# Microcontroller.net
KiCad netlist of a schematic drawn in Altium Designer
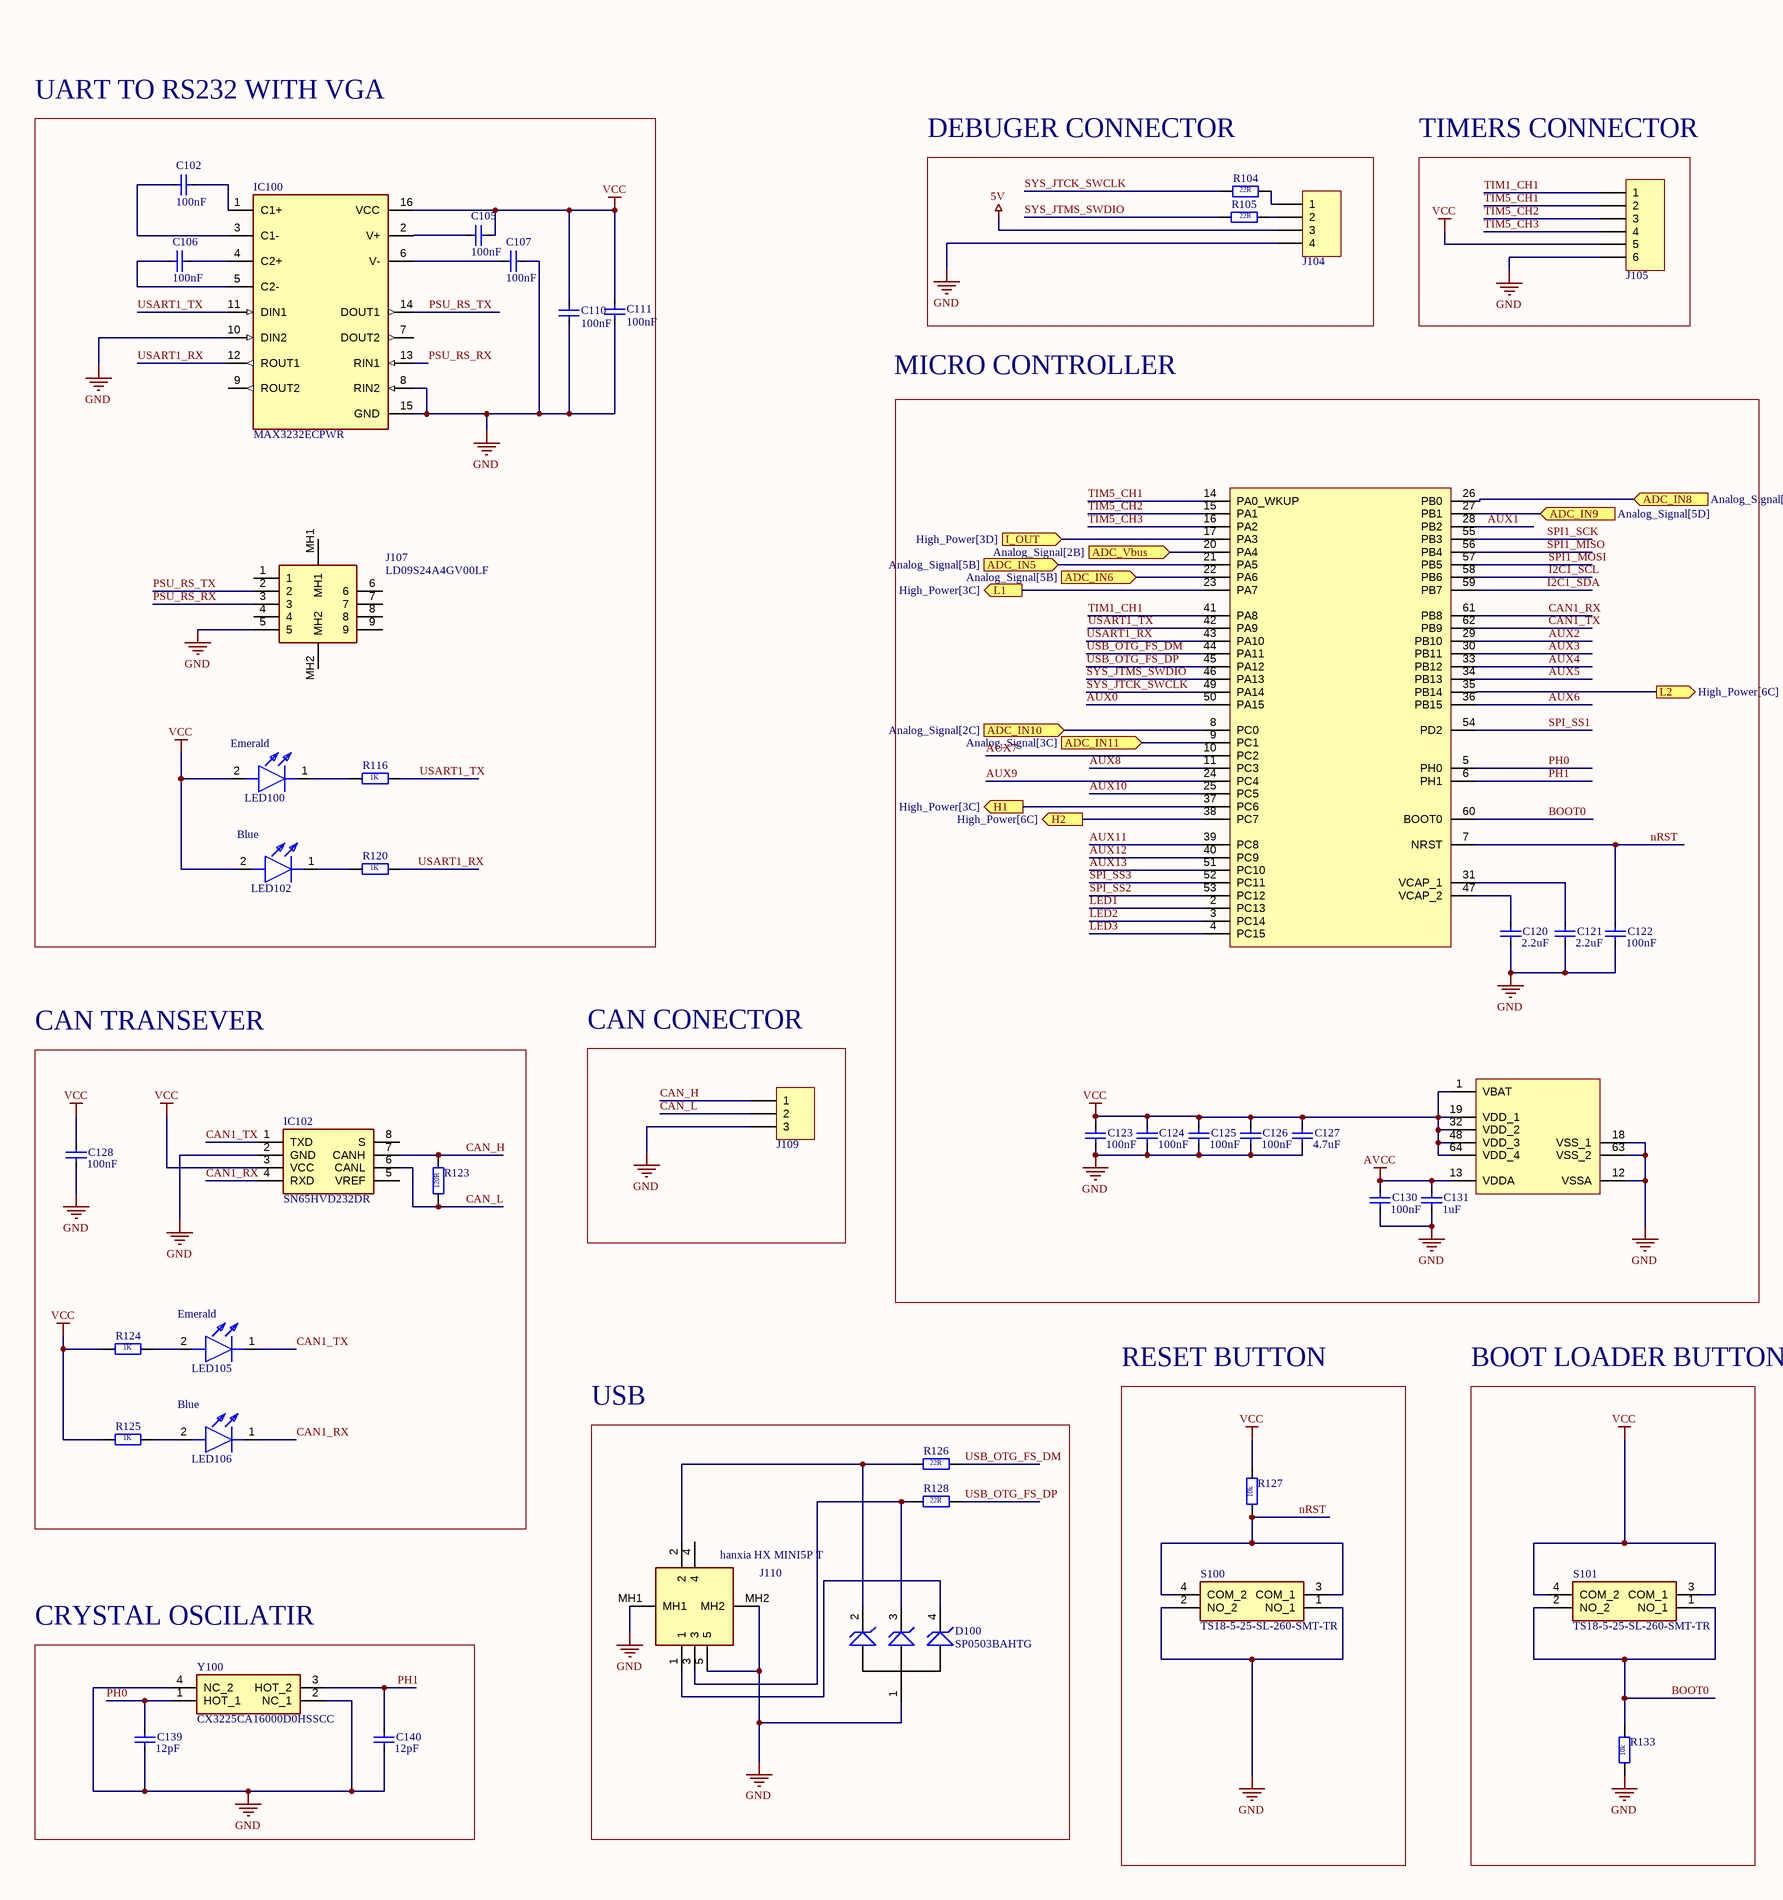
[diagram p0: Microcontroller.SchDoc, left]
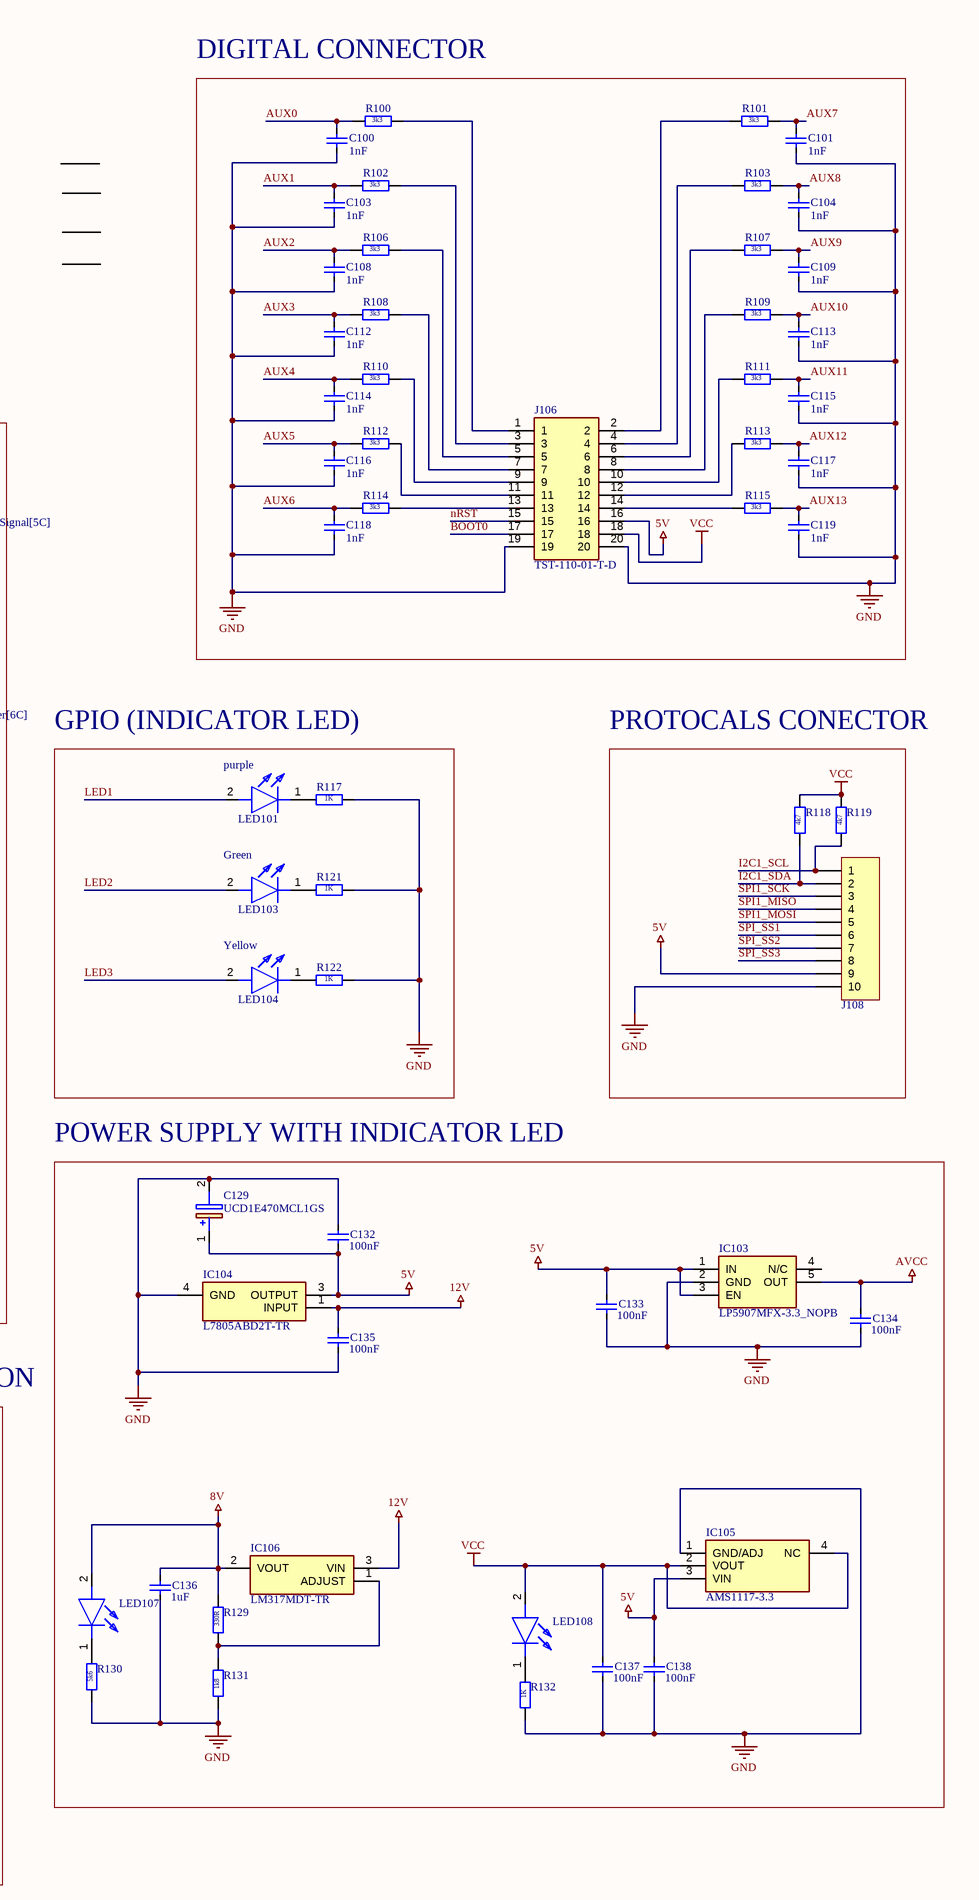
[diagram p1: Microcontroller.SchDoc, right]

(export (version "E")
  (design (tool "Eeschema 10.0.6"))
  (components
    (comp (ref "C100")
      (value "1nF")
      (footprint "CAPC1608X09N")
      (fields (field (name "MPN") "CC0603KRX7R9BB102") (field (name "Comment") "C"))
      (libsource (lib "My_lib") (part "C"))
    )
    (comp (ref "C101")
      (value "1nF")
      (footprint "CAPC1608X09N")
      (fields (field (name "MPN") "CC0603KRX7R9BB102") (field (name "Comment") "C"))
      (libsource (lib "My_lib") (part "C"))
    )
    (comp (ref "C102")
      (value "100nF")
      (footprint "CAPC1608X09N")
      (fields (field (name "MPN") "06033C104KAT4A") (field (name "Comment") "C"))
      (libsource (lib "My_lib") (part "C"))
    )
    (comp (ref "C103")
      (value "1nF")
      (footprint "CAPC1608X09N")
      (fields (field (name "MPN") "CC0603KRX7R9BB102") (field (name "Comment") "C"))
      (libsource (lib "My_lib") (part "C"))
    )
    (comp (ref "C104")
      (value "1nF")
      (footprint "CAPC1608X09N")
      (fields (field (name "MPN") "CC0603KRX7R9BB102") (field (name "Comment") "C"))
      (libsource (lib "My_lib") (part "C"))
    )
    (comp (ref "C105")
      (value "100nF")
      (footprint "CAPC1608X09N")
      (fields (field (name "MPN") "06033C104KAT4A") (field (name "Comment") "C"))
      (libsource (lib "My_lib") (part "C"))
    )
    (comp (ref "C106")
      (value "100nF")
      (footprint "CAPC1608X09N")
      (fields (field (name "MPN") "06033C104KAT4A") (field (name "Comment") "C"))
      (libsource (lib "My_lib") (part "C"))
    )
    (comp (ref "C107")
      (value "100nF")
      (footprint "CAPC1608X09N")
      (fields (field (name "MPN") "06033C104KAT4A") (field (name "Comment") "C"))
      (libsource (lib "My_lib") (part "C"))
    )
    (comp (ref "C108")
      (value "1nF")
      (footprint "CAPC1608X09N")
      (fields (field (name "MPN") "CC0603KRX7R9BB102") (field (name "Comment") "C"))
      (libsource (lib "My_lib") (part "C"))
    )
    (comp (ref "C109")
      (value "1nF")
      (footprint "CAPC1608X09N")
      (fields (field (name "MPN") "CC0603KRX7R9BB102") (field (name "Comment") "C"))
      (libsource (lib "My_lib") (part "C"))
    )
    (comp (ref "C110")
      (value "100nF")
      (footprint "CAPC1608X09N")
      (fields (field (name "MPN") "06033C104KAT4A") (field (name "Comment") "C"))
      (libsource (lib "My_lib") (part "C"))
    )
    (comp (ref "C111")
      (value "100nF")
      (footprint "CAPC1608X09N")
      (fields (field (name "MPN") "06033C104KAT4A") (field (name "Comment") "C"))
      (libsource (lib "My_lib") (part "C"))
    )
    (comp (ref "C112")
      (value "1nF")
      (footprint "CAPC1608X09N")
      (fields (field (name "MPN") "CC0603KRX7R9BB102") (field (name "Comment") "C"))
      (libsource (lib "My_lib") (part "C"))
    )
    (comp (ref "C113")
      (value "1nF")
      (footprint "CAPC1608X09N")
      (fields (field (name "MPN") "CC0603KRX7R9BB102") (field (name "Comment") "C"))
      (libsource (lib "My_lib") (part "C"))
    )
    (comp (ref "C114")
      (value "1nF")
      (footprint "CAPC1608X09N")
      (fields (field (name "MPN") "CC0603KRX7R9BB102") (field (name "Comment") "C"))
      (libsource (lib "My_lib") (part "C"))
    )
    (comp (ref "C115")
      (value "1nF")
      (footprint "CAPC1608X09N")
      (fields (field (name "MPN") "CC0603KRX7R9BB102") (field (name "Comment") "C"))
      (libsource (lib "My_lib") (part "C"))
    )
    (comp (ref "C116")
      (value "1nF")
      (footprint "CAPC1608X09N")
      (fields (field (name "MPN") "CC0603KRX7R9BB102") (field (name "Comment") "C"))
      (libsource (lib "My_lib") (part "C"))
    )
    (comp (ref "C117")
      (value "1nF")
      (footprint "CAPC1608X09N")
      (fields (field (name "MPN") "CC0603KRX7R9BB102") (field (name "Comment") "C"))
      (libsource (lib "My_lib") (part "C"))
    )
    (comp (ref "C118")
      (value "1nF")
      (footprint "CAPC1608X09N")
      (fields (field (name "MPN") "CC0603KRX7R9BB102") (field (name "Comment") "C"))
      (libsource (lib "My_lib") (part "C"))
    )
    (comp (ref "C119")
      (value "1nF")
      (footprint "CAPC1608X09N")
      (fields (field (name "MPN") "CC0603KRX7R9BB102") (field (name "Comment") "C"))
      (libsource (lib "My_lib") (part "C"))
    )
    (comp (ref "C120")
      (value "2.2uF")
      (footprint "CAPC1608X09N")
      (fields (field (name "MPN") "0603B225K250NT") (field (name "Comment") "C"))
      (libsource (lib "My_lib") (part "C"))
    )
    (comp (ref "C121")
      (value "2.2uF")
      (footprint "CAPC1608X09N")
      (fields (field (name "MPN") "0603B225K250NT") (field (name "Comment") "C"))
      (libsource (lib "My_lib") (part "C"))
    )
    (comp (ref "C122")
      (value "100nF")
      (footprint "CAPC1608X09N")
      (fields (field (name "MPN") "06033C104KAT4A") (field (name "Comment") "C"))
      (libsource (lib "My_lib") (part "C"))
    )
    (comp (ref "C123")
      (value "100nF")
      (footprint "CAPC1608X09N")
      (fields (field (name "MPN") "06033C104KAT4A") (field (name "Comment") "C"))
      (libsource (lib "My_lib") (part "C"))
    )
    (comp (ref "C124")
      (value "100nF")
      (footprint "CAPC1608X09N")
      (fields (field (name "MPN") "06033C104KAT4A") (field (name "Comment") "C"))
      (libsource (lib "My_lib") (part "C"))
    )
    (comp (ref "C125")
      (value "100nF")
      (footprint "CAPC1608X09N")
      (fields (field (name "MPN") "06033C104KAT4A") (field (name "Comment") "C"))
      (libsource (lib "My_lib") (part "C"))
    )
    (comp (ref "C126")
      (value "100nF")
      (footprint "CAPC1608X09N")
      (fields (field (name "MPN") "06033C104KAT4A") (field (name "Comment") "C"))
      (libsource (lib "My_lib") (part "C"))
    )
    (comp (ref "C127")
      (value "4.7uF")
      (footprint "CAPC3216X18N")
      (fields (field (name "MPN") "CS3216X7R475K160NRI") (field (name "Comment") "C"))
      (libsource (lib "My_lib") (part "C"))
    )
    (comp (ref "C128")
      (value "100nF")
      (footprint "CAPC1608X09N")
      (fields (field (name "MPN") "06033C104KAT4A") (field (name "Comment") "C"))
      (libsource (lib "My_lib") (part "C"))
    )
    (comp (ref "C129")
      (value "UCD1E470MCL1GS")
      (footprint "SamacSys:CAPAE660X610N")
      (description "Capacitor Polarised")
      (fields (field (name "LCSC PART NUMBER") "C308827"))
      (libsource (lib "*") (part "UCD1E470MCL1GS"))
    )
    (comp (ref "C130")
      (value "100nF")
      (footprint "CAPC1608X09N")
      (fields (field (name "MPN") "06033C104KAT4A") (field (name "Comment") "C"))
      (libsource (lib "My_lib") (part "C"))
    )
    (comp (ref "C131")
      (value "1uF")
      (footprint "CAPC1608X09N")
      (fields (field (name "MPN") "CL10B105KP8NNNC") (field (name "Comment") "C"))
      (libsource (lib "My_lib") (part "C"))
    )
    (comp (ref "C132")
      (value "100nF")
      (footprint "CAPC1608X09N")
      (fields (field (name "MPN") "06033C104KAT4A") (field (name "Comment") "C"))
      (libsource (lib "My_lib") (part "C"))
    )
    (comp (ref "C133")
      (value "100nF")
      (footprint "CAPC1608X09N")
      (fields (field (name "MPN") "06033C104KAT4A") (field (name "Comment") "C"))
      (libsource (lib "My_lib") (part "C"))
    )
    (comp (ref "C134")
      (value "100nF")
      (footprint "CAPC1608X09N")
      (fields (field (name "MPN") "06033C104KAT4A") (field (name "Comment") "C"))
      (libsource (lib "My_lib") (part "C"))
    )
    (comp (ref "C135")
      (value "100nF")
      (footprint "CAPC1608X09N")
      (fields (field (name "MPN") "06033C104KAT4A") (field (name "Comment") "C"))
      (libsource (lib "My_lib") (part "C"))
    )
    (comp (ref "C136")
      (value "1uF")
      (footprint "CAPC1608X09N")
      (fields (field (name "MPN") "CL10B105KP8NNNC") (field (name "Comment") "C"))
      (libsource (lib "My_lib") (part "C"))
    )
    (comp (ref "C137")
      (value "100nF")
      (footprint "CAPC1608X09N")
      (fields (field (name "MPN") "06033C104KAT4A") (field (name "Comment") "C"))
      (libsource (lib "My_lib") (part "C"))
    )
    (comp (ref "C138")
      (value "100nF")
      (footprint "CAPC1608X09N")
      (fields (field (name "MPN") "06033C104KAT4A") (field (name "Comment") "C"))
      (libsource (lib "My_lib") (part "C"))
    )
    (comp (ref "C139")
      (value "12pF")
      (footprint "CAPC1608X09N")
      (fields (field (name "MPN") "CL10C120JB8NNNC") (field (name "Comment") "C"))
      (libsource (lib "My_lib") (part "C"))
    )
    (comp (ref "C140")
      (value "12pF")
      (footprint "CAPC1608X09N")
      (fields (field (name "MPN") "CL10C120JB8NNNC") (field (name "Comment") "C"))
      (libsource (lib "My_lib") (part "C"))
    )
    (comp (ref "D100")
      (value "SP0503BAHTG")
      (footprint "SamacSys:SP0503BAHTG")
      (description "TVS Diode (Uni-directional)")
      (fields (field (name "LCSC PART NUMBER") "C41364459"))
      (libsource (lib "SamacSys") (part "SP0503BAHTG"))
    )
    (comp (ref "IC100")
      (value "MAX3232ECPWR")
      (footprint "SamacSys:SOP65P640X120-16N")
      (description "Integrated Circuit")
      (fields (field (name "LCSC PART NUMBER") "C11317"))
      (libsource (lib "SamacSys") (part "MAX3232ECPWR"))
    )
    (comp (ref "IC101")
      (value "STM32F405RGT6")
      (footprint "SamacSys:QFP50P1200X1200X160-64N")
      (description "Integrated Circuit")
      (fields
        (field (name "LCSC PART NUMBER") "C15742")
        (field (name "MOUSER PART NUMBER") "511-STM32F405RGT6")
      )
      (libsource (lib "SamacSys") (part "STM32F405RGT6"))
    )
    (comp (ref "IC102")
      (value "SN65HVD232DR")
      (footprint "SamacSys:SOIC127P600X175-8N")
      (description "Integrated Circuit")
      (fields (field (name "LCSC PART NUMBER") "C30530"))
      (libsource (lib "*") (part "TJA1050T_CM"))
    )
    (comp (ref "IC103")
      (value "LP5907MFX-3.3_NOPB")
      (footprint "SamacSys:SOT95P280X145-5N")
      (description "Integrated Circuit")
      (fields (field (name "MPN") "LP5907MFX-3.3/NOPB") (field (name "LCSC PART NUMBER") "C80670"))
      (libsource (lib "SamacSys") (part "LP5907MFX-3.3_NOPB"))
    )
    (comp (ref "IC104")
      (value "L7805ABD2T-TR")
      (footprint "SamacSys:D2PAK-STB35NF10T4")
      (description "Integrated Circuit")
      (fields (field (name "LCSC PART NUMBER") "C86206"))
      (libsource (lib "SamacSys") (part "L7805ABD2T-TR"))
    )
    (comp (ref "IC105")
      (value "AMS1117-3.3")
      (footprint "SamacSys:SOT229P700X180-4N")
      (description "Integrated Circuit")
      (fields (field (name "LCSC PART NUMBER") "C347222"))
      (libsource (lib "SamacSys") (part "AMS1117-3.3"))
    )
    (comp (ref "IC106")
      (value "LM317MDT-TR")
      (footprint "SamacSys:STD70N10F4")
      (description "Integrated Circuit")
      (fields (field (name "LCSC PART NUMBER") "C68136"))
      (libsource (lib "*") (part "LM317MDT-TR"))
    )
    (comp (ref "J100") (value "Hole") (footprint "Hole") (libsource (lib "My_lib") (part "Hole")))
    (comp (ref "J101") (value "Hole") (footprint "Hole") (libsource (lib "My_lib") (part "Hole")))
    (comp (ref "J102") (value "Hole") (footprint "Hole") (libsource (lib "My_lib") (part "Hole")))
    (comp (ref "J103") (value "Hole") (footprint "Hole") (libsource (lib "My_lib") (part "Hole")))
    (comp (ref "J104")
      (value "XH2.54-4P")
      (footprint "XH2.54-4P")
      (fields (field (name "MPN") "BX-XH2.54-4PZZ"))
      (libsource (lib "My_lib") (part "XH2.54-4P"))
    )
    (comp (ref "J105")
      (value "XH2.54-6P")
      (footprint "XH2.54-6P")
      (fields (field (name "MPN") "BX-XH2.54-6PZZ"))
      (libsource (lib "My_lib") (part "XH2.54-6P"))
    )
    (comp (ref "J106")
      (value "TST-110-01-T-D")
      (footprint "SamacSys:TST-110-XX-Y-D")
      (description "Connector")
      (fields (field (name "MPN") "BH254V-20P") (field (name "LCSC PART NUMBER") "C492444"))
      (libsource (lib "SamacSys") (part "TST-110-01-T-D"))
    )
    (comp (ref "J107")
      (value "LD09S24A4GV00LF")
      (footprint "SamacSys:LD09S24A4GV00LF")
      (description "Connector")
      (fields (field (name "MPN") "DS1034-09FUNSi44") (field (name "LCSC PART NUMBER") "C77831"))
      (libsource (lib "SamacSys") (part "LD09S24A4GV00LF"))
    )
    (comp (ref "J108")
      (value "XH2.54-10P")
      (footprint "XH2.54-10P")
      (fields (field (name "MPN") "BX-XH2.54-10PZZ"))
      (libsource (lib "My_lib") (part "XH2.54-10P"))
    )
    (comp (ref "J109")
      (value "XH2.54-3P")
      (footprint "XH2.54-3P")
      (fields (field (name "MPN") "BX-XH2.54-3PZZ"))
      (libsource (lib "My_lib") (part "XH2.54-3P"))
    )
    (comp (ref "J110")
      (value "hanxia HX MINI5P T")
      (footprint "SamacSys:10119313301TLF")
      (description "Connector")
      (fields (field (name "MPN") "HX MINI5P T") (field (name "LCSC PART NUMBER") "C19189146"))
      (libsource (lib "*") (part "10119313-301TLF"))
    )
    (comp (ref "LED100")
      (value "Emerald")
      (footprint "SamacSys:LEDC1608X80N")
      (description "LED")
      (fields (field (name "MPN") "XL-1608UGC-04") (field (name "LCSC PART NUMBER") "C965804"))
      (libsource (lib "SamacSys") (part "LTST-C190KGKT"))
    )
    (comp (ref "LED101")
      (value "purple")
      (footprint "SamacSys:LEDC1608X80N")
      (description "LED")
      (fields (field (name "MPN") "XL-1608UVC-04") (field (name "LCSC PART NUMBER") "C7371898"))
      (libsource (lib "SamacSys") (part "LTST-C190KGKT"))
    )
    (comp (ref "LED102")
      (value "Blue")
      (footprint "SamacSys:LEDC1608X80N")
      (description "LED")
      (fields (field (name "MPN") "XL-1608UBC-04") (field (name "LCSC PART NUMBER") "C965807"))
      (libsource (lib "SamacSys") (part "LTST-C190KGKT"))
    )
    (comp (ref "LED103")
      (value "Green")
      (footprint "SamacSys:LEDC1608X80N")
      (description "LED")
      (fields (field (name "MPN") "XL-1608BGWC-06") (field (name "LCSC PART NUMBER") "C965809"))
      (libsource (lib "SamacSys") (part "LTST-C190KGKT"))
    )
    (comp (ref "LED104")
      (value "Yellow")
      (footprint "SamacSys:LEDC1608X80N")
      (description "LED")
      (fields (field (name "MPN") "XL-1608WYC-06") (field (name "LCSC PART NUMBER") "C7371907"))
      (libsource (lib "SamacSys") (part "LTST-C190KGKT"))
    )
    (comp (ref "LED105")
      (value "Emerald")
      (footprint "SamacSys:LEDC1608X80N")
      (description "LED")
      (fields (field (name "MPN") "XL-1608UGC-04") (field (name "LCSC PART NUMBER") "C965804"))
      (libsource (lib "SamacSys") (part "LTST-C190KGKT"))
    )
    (comp (ref "LED106")
      (value "Blue")
      (footprint "SamacSys:LEDC1608X80N")
      (description "LED")
      (fields (field (name "MPN") "XL-1608UBC-04") (field (name "LCSC PART NUMBER") "C965807"))
      (libsource (lib "SamacSys") (part "LTST-C190KGKT"))
    )
    (comp (ref "LED107")
      (value "LTST-C190KGKT")
      (footprint "SamacSys:LEDC1608X80N")
      (description "LED")
      (fields (field (name "MPN") "XL-1608SURC-06") (field (name "LCSC PART NUMBER") "C965799"))
      (libsource (lib "SamacSys") (part "LTST-C190KGKT"))
    )
    (comp (ref "LED108")
      (value "LTST-C190KGKT")
      (footprint "SamacSys:LEDC1608X80N")
      (description "LED")
      (fields (field (name "MPN") "XL-1608SURC-06") (field (name "LCSC PART NUMBER") "C965799"))
      (libsource (lib "SamacSys") (part "LTST-C190KGKT"))
    )
    (comp (ref "R100")
      (value "3k3")
      (footprint "RESC1608X06N")
      (fields (field (name "MPN") "0603WAF3301T5E") (field (name "Comment") "R"))
      (libsource (lib "") (part "R_1"))
    )
    (comp (ref "R101")
      (value "3k3")
      (footprint "RESC1608X06N")
      (fields (field (name "MPN") "0603WAF3301T5E") (field (name "Comment") "R"))
      (libsource (lib "") (part "R_2"))
    )
    (comp (ref "R102")
      (value "3k3")
      (footprint "RESC1608X06N")
      (fields (field (name "MPN") "0603WAF3301T5E") (field (name "Comment") "R"))
      (libsource (lib "") (part "R_1"))
    )
    (comp (ref "R103")
      (value "3k3")
      (footprint "RESC1608X06N")
      (fields (field (name "MPN") "0603WAF3301T5E") (field (name "Comment") "R"))
      (libsource (lib "") (part "R_2"))
    )
    (comp (ref "R104")
      (value "22R")
      (footprint "RESC1608X06N")
      (fields (field (name "MPN") "0603WAF220JT5E") (field (name "Comment") "R"))
      (libsource (lib "") (part "R_1"))
    )
    (comp (ref "R105")
      (value "22R")
      (footprint "RESC1608X06N")
      (fields (field (name "MPN") "0603WAF220JT5E") (field (name "Comment") "R"))
      (libsource (lib "") (part "R_1"))
    )
    (comp (ref "R106")
      (value "3k3")
      (footprint "RESC1608X06N")
      (fields (field (name "MPN") "0603WAF3301T5E") (field (name "Comment") "R"))
      (libsource (lib "") (part "R_1"))
    )
    (comp (ref "R107")
      (value "3k3")
      (footprint "RESC1608X06N")
      (fields (field (name "MPN") "0603WAF3301T5E") (field (name "Comment") "R"))
      (libsource (lib "") (part "R_2"))
    )
    (comp (ref "R108")
      (value "3k3")
      (footprint "RESC1608X06N")
      (fields (field (name "MPN") "0603WAF3301T5E") (field (name "Comment") "R"))
      (libsource (lib "") (part "R_1"))
    )
    (comp (ref "R109")
      (value "3k3")
      (footprint "RESC1608X06N")
      (fields (field (name "MPN") "0603WAF3301T5E") (field (name "Comment") "R"))
      (libsource (lib "") (part "R_2"))
    )
    (comp (ref "R110")
      (value "3k3")
      (footprint "RESC1608X06N")
      (fields (field (name "MPN") "0603WAF3301T5E") (field (name "Comment") "R"))
      (libsource (lib "") (part "R_1"))
    )
    (comp (ref "R111")
      (value "3k3")
      (footprint "RESC1608X06N")
      (fields (field (name "MPN") "0603WAF3301T5E") (field (name "Comment") "R"))
      (libsource (lib "") (part "R_2"))
    )
    (comp (ref "R112")
      (value "3k3")
      (footprint "RESC1608X06N")
      (fields (field (name "MPN") "0603WAF3301T5E") (field (name "Comment") "R"))
      (libsource (lib "") (part "R_1"))
    )
    (comp (ref "R113")
      (value "3k3")
      (footprint "RESC1608X06N")
      (fields (field (name "MPN") "0603WAF3301T5E") (field (name "Comment") "R"))
      (libsource (lib "") (part "R_2"))
    )
    (comp (ref "R114")
      (value "3k3")
      (footprint "RESC1608X06N")
      (fields (field (name "MPN") "0603WAF3301T5E") (field (name "Comment") "R"))
      (libsource (lib "") (part "R_1"))
    )
    (comp (ref "R115")
      (value "3k3")
      (footprint "RESC1608X06N")
      (fields (field (name "MPN") "0603WAF3301T5E") (field (name "Comment") "R"))
      (libsource (lib "") (part "R_2"))
    )
    (comp (ref "R116")
      (value "1K")
      (footprint "RESC1608X06N")
      (fields (field (name "MPN") "0603WAF1001T5E") (field (name "Comment") "R"))
      (libsource (lib "") (part "R_1"))
    )
    (comp (ref "R117")
      (value "1K")
      (footprint "RESC1608X06N")
      (fields (field (name "MPN") "0603WAF1001T5E") (field (name "Comment") "R"))
      (libsource (lib "") (part "R_1"))
    )
    (comp (ref "R118")
      (value "4k7")
      (footprint "RESC3216X07N")
      (fields (field (name "MPN") "RC0603FR-074K7L") (field (name "Comment") "R"))
      (libsource (lib "My_lib") (part "R"))
    )
    (comp (ref "R119")
      (value "4k7")
      (footprint "RESC3216X07N")
      (fields (field (name "MPN") "RC0603FR-074K7L") (field (name "Comment") "R"))
      (libsource (lib "My_lib") (part "R"))
    )
    (comp (ref "R120")
      (value "1K")
      (footprint "RESC1608X06N")
      (fields (field (name "MPN") "0603WAF1001T5E") (field (name "Comment") "R"))
      (libsource (lib "") (part "R_1"))
    )
    (comp (ref "R121")
      (value "1K")
      (footprint "RESC1608X06N")
      (fields (field (name "MPN") "0603WAF1001T5E") (field (name "Comment") "R"))
      (libsource (lib "") (part "R_1"))
    )
    (comp (ref "R122")
      (value "1K")
      (footprint "RESC1608X06N")
      (fields (field (name "MPN") "0603WAF1001T5E") (field (name "Comment") "R"))
      (libsource (lib "") (part "R_1"))
    )
    (comp (ref "R123")
      (value "120R")
      (footprint "RESC1608X06N")
      (fields (field (name "MPN") "0603WAF1200T5E") (field (name "Comment") "R"))
      (libsource (lib "My_lib") (part "R"))
    )
    (comp (ref "R124")
      (value "1K")
      (footprint "RESC1608X06N")
      (fields (field (name "MPN") "0603WAF1001T5E") (field (name "Comment") "R"))
      (libsource (lib "") (part "R_1"))
    )
    (comp (ref "R125")
      (value "1K")
      (footprint "RESC1608X06N")
      (fields (field (name "MPN") "0603WAF1001T5E") (field (name "Comment") "R"))
      (libsource (lib "") (part "R_1"))
    )
    (comp (ref "R126")
      (value "22R")
      (footprint "RESC1608X06N")
      (fields (field (name "MPN") "0603WAF220JT5E") (field (name "Comment") "R"))
      (libsource (lib "") (part "R_1"))
    )
    (comp (ref "R127")
      (value "10k")
      (footprint "RESC1608X06N")
      (fields (field (name "MPN") "RC0603FR-0710KL") (field (name "Comment") "R"))
      (libsource (lib "My_lib") (part "R"))
    )
    (comp (ref "R128")
      (value "22R")
      (footprint "RESC1608X06N")
      (fields (field (name "MPN") "0603WAF220JT5E") (field (name "Comment") "R"))
      (libsource (lib "") (part "R_1"))
    )
    (comp (ref "R129")
      (value "330R")
      (footprint "RESC1608X06N")
      (fields (field (name "MPN") "0805W8F3300T5E") (field (name "Comment") "R"))
      (libsource (lib "My_lib") (part "R"))
    )
    (comp (ref "R130")
      (value "5k6")
      (footprint "RESC1608X06N")
      (fields (field (name "MPN") "0603WAF5601T5E") (field (name "Comment") "R"))
      (libsource (lib "My_lib") (part "R"))
    )
    (comp (ref "R131")
      (value "1k8")
      (footprint "RESC1608X06N")
      (fields (field (name "MPN") "0603WAF1801T5E") (field (name "Comment") "R"))
      (libsource (lib "My_lib") (part "R"))
    )
    (comp (ref "R132")
      (value "1K")
      (footprint "RESC1608X06N")
      (fields (field (name "MPN") "0603WAF1001T5E") (field (name "Comment") "R"))
      (libsource (lib "My_lib") (part "R"))
    )
    (comp (ref "R133")
      (value "10k")
      (footprint "RESC1608X06N")
      (fields (field (name "MPN") "RC0603FR-0710KL") (field (name "Comment") "R"))
      (libsource (lib "My_lib") (part "R"))
    )
    (comp (ref "S100")
      (value "TS18-5-25-SL-260-SMT-TR")
      (footprint "SamacSys:TS18525SL260SMTTR")
      (description "Switch")
      (fields (field (name "MPN") "GT-TC084B-H015-L5") (field (name "LCSC PART NUMBER") "C778173"))
      (libsource (lib "*") (part "TS18-5-25-SL-260-SMT-TR"))
    )
    (comp (ref "S101")
      (value "TS18-5-25-SL-260-SMT-TR")
      (footprint "SamacSys:TS18525SL260SMTTR")
      (description "Switch")
      (fields (field (name "MPN") "GT-TC084B-H015-L5") (field (name "LCSC PART NUMBER") "C778173"))
      (libsource (lib "*") (part "TS18-5-25-SL-260-SMT-TR"))
    )
    (comp (ref "Y100")
      (value "CX3225CA16000D0HSSCC")
      (footprint "SamacSys:CX3225CA16000D0HSSCC")
      (description "Crystal or Oscillator")
      (fields (field (name "MPN") "XL2EL89COI-111YLC-8M") (field (name "LCSC PART NUMBER") "C2973805"))
      (libsource (lib "SamacSys") (part "CX3225CA16000D0HSSCC"))
    )
  )
  (nets
    (net (code "1") (name "/ADC_IN5") (class "Default")
      (node (ref "IC101") (pin "21") (pinfunction "PA5_21") (pintype "passive"))
    )
    (net (code "2") (name "/ADC_IN6") (class "Default")
      (node (ref "IC101") (pin "22") (pinfunction "PA6_22") (pintype "passive"))
    )
    (net (code "3") (name "/ADC_IN8") (class "Default")
      (node (ref "IC101") (pin "26") (pinfunction "PB0_26") (pintype "passive"))
    )
    (net (code "4") (name "/ADC_IN9") (class "Default")
      (node (ref "IC101") (pin "27") (pinfunction "PB1_27") (pintype "passive"))
    )
    (net (code "5") (name "/ADC_IN10") (class "Default")
      (node (ref "IC101") (pin "8") (pinfunction "PC0_8") (pintype "passive"))
    )
    (net (code "6") (name "/ADC_IN11") (class "Default")
      (node (ref "IC101") (pin "9") (pinfunction "PC1_9") (pintype "passive"))
    )
    (net (code "7") (name "/ADC_Vbus") (class "Default")
      (node (ref "IC101") (pin "20") (pinfunction "PA4_20") (pintype "passive"))
    )
    (net (code "8") (name "/AUX0") (class "Default")
      (node (ref "C100") (pin "2") (pinfunction "2_2") (pintype "passive"))
      (node (ref "IC101") (pin "50") (pinfunction "PA15_50") (pintype "passive"))
      (node (ref "R100") (pin "1") (pinfunction "1_1") (pintype "passive"))
    )
    (net (code "9") (name "/AUX1") (class "Default")
      (node (ref "C103") (pin "2") (pinfunction "2_2") (pintype "passive"))
      (node (ref "IC101") (pin "28") (pinfunction "PB2_28") (pintype "passive"))
      (node (ref "R102") (pin "1") (pinfunction "1_1") (pintype "passive"))
    )
    (net (code "10") (name "/AUX2") (class "Default")
      (node (ref "C108") (pin "2") (pinfunction "2_2") (pintype "passive"))
      (node (ref "IC101") (pin "29") (pinfunction "PB10_29") (pintype "passive"))
      (node (ref "R106") (pin "1") (pinfunction "1_1") (pintype "passive"))
    )
    (net (code "11") (name "/AUX3") (class "Default")
      (node (ref "C112") (pin "2") (pinfunction "2_2") (pintype "passive"))
      (node (ref "IC101") (pin "30") (pinfunction "PB11_30") (pintype "passive"))
      (node (ref "R108") (pin "1") (pinfunction "1_1") (pintype "passive"))
    )
    (net (code "12") (name "/AUX4") (class "Default")
      (node (ref "C114") (pin "2") (pinfunction "2_2") (pintype "passive"))
      (node (ref "IC101") (pin "33") (pinfunction "PB12_33") (pintype "passive"))
      (node (ref "R110") (pin "1") (pinfunction "1_1") (pintype "passive"))
    )
    (net (code "13") (name "/AUX5") (class "Default")
      (node (ref "C116") (pin "2") (pinfunction "2_2") (pintype "passive"))
      (node (ref "IC101") (pin "34") (pinfunction "PB13_34") (pintype "passive"))
      (node (ref "R112") (pin "1") (pinfunction "1_1") (pintype "passive"))
    )
    (net (code "14") (name "/AUX6") (class "Default")
      (node (ref "C118") (pin "2") (pinfunction "2_2") (pintype "passive"))
      (node (ref "IC101") (pin "36") (pinfunction "PB15_36") (pintype "passive"))
      (node (ref "R114") (pin "1") (pinfunction "1_1") (pintype "passive"))
    )
    (net (code "15") (name "/AUX7") (class "Default")
      (node (ref "C101") (pin "2") (pinfunction "2_2") (pintype "passive"))
      (node (ref "IC101") (pin "10") (pinfunction "PC2_10") (pintype "passive"))
      (node (ref "R101") (pin "1") (pinfunction "1_1") (pintype "passive"))
    )
    (net (code "16") (name "/AUX8") (class "Default")
      (node (ref "C104") (pin "2") (pinfunction "2_2") (pintype "passive"))
      (node (ref "IC101") (pin "11") (pinfunction "PC3_11") (pintype "passive"))
      (node (ref "R103") (pin "1") (pinfunction "1_1") (pintype "passive"))
    )
    (net (code "17") (name "/AUX9") (class "Default")
      (node (ref "C109") (pin "2") (pinfunction "2_2") (pintype "passive"))
      (node (ref "IC101") (pin "24") (pinfunction "PC4_24") (pintype "passive"))
      (node (ref "R107") (pin "1") (pinfunction "1_1") (pintype "passive"))
    )
    (net (code "18") (name "/AUX10") (class "Default")
      (node (ref "C113") (pin "2") (pinfunction "2_2") (pintype "passive"))
      (node (ref "IC101") (pin "25") (pinfunction "PC5_25") (pintype "passive"))
      (node (ref "R109") (pin "1") (pinfunction "1_1") (pintype "passive"))
    )
    (net (code "19") (name "/AUX11") (class "Default")
      (node (ref "C115") (pin "2") (pinfunction "2_2") (pintype "passive"))
      (node (ref "IC101") (pin "39") (pinfunction "PC8_39") (pintype "passive"))
      (node (ref "R111") (pin "1") (pinfunction "1_1") (pintype "passive"))
    )
    (net (code "20") (name "/AUX12") (class "Default")
      (node (ref "C117") (pin "2") (pinfunction "2_2") (pintype "passive"))
      (node (ref "IC101") (pin "40") (pinfunction "PC9_40") (pintype "passive"))
      (node (ref "R113") (pin "1") (pinfunction "1_1") (pintype "passive"))
    )
    (net (code "21") (name "/AUX13") (class "Default")
      (node (ref "C119") (pin "2") (pinfunction "2_2") (pintype "passive"))
      (node (ref "IC101") (pin "51") (pinfunction "PC10_51") (pintype "passive"))
      (node (ref "R115") (pin "1") (pinfunction "1_1") (pintype "passive"))
    )
    (net (code "22") (name "/BOOT0") (class "Default")
      (node (ref "IC101") (pin "60") (pinfunction "BOOT0_60") (pintype "passive"))
      (node (ref "J106") (pin "17") (pinfunction "17_17") (pintype "passive"))
      (node (ref "R133") (pin "2") (pinfunction "2_2") (pintype "passive"))
      (node (ref "S101") (pin "1") (pinfunction "NO_1_1") (pintype "passive"))
      (node (ref "S101") (pin "2") (pinfunction "NO_2_2") (pintype "passive"))
    )
    (net (code "23") (name "/CAN1_RX") (class "Default")
      (node (ref "IC101") (pin "61") (pinfunction "PB8_61") (pintype "passive"))
      (node (ref "IC102") (pin "4") (pinfunction "RXD_4") (pintype "passive"))
      (node (ref "LED106") (pin "1") (pinfunction "K_1") (pintype "passive"))
    )
    (net (code "24") (name "/CAN1_TX") (class "Default")
      (node (ref "IC101") (pin "62") (pinfunction "PB9_62") (pintype "passive"))
      (node (ref "IC102") (pin "1") (pinfunction "TXD_1") (pintype "passive"))
      (node (ref "LED105") (pin "1") (pinfunction "K_1") (pintype "passive"))
    )
    (net (code "25") (name "/CAN_H") (class "Default")
      (node (ref "IC102") (pin "7") (pinfunction "CANH_7") (pintype "passive"))
      (node (ref "J109") (pin "1") (pinfunction "1_1") (pintype "passive"))
      (node (ref "R123") (pin "2") (pinfunction "2_2") (pintype "passive"))
    )
    (net (code "26") (name "/CAN_L") (class "Default")
      (node (ref "IC102") (pin "6") (pinfunction "CANL_6") (pintype "passive"))
      (node (ref "J109") (pin "2") (pinfunction "2_2") (pintype "passive"))
      (node (ref "R123") (pin "1") (pinfunction "1_1") (pintype "passive"))
    )
    (net (code "27") (name "/H1") (class "Default")
      (node (ref "IC101") (pin "37") (pinfunction "PC6_37") (pintype "passive"))
    )
    (net (code "28") (name "/H2") (class "Default")
      (node (ref "IC101") (pin "38") (pinfunction "PC7_38") (pintype "passive"))
    )
    (net (code "29") (name "/I2C1_SCL") (class "Default")
      (node (ref "IC101") (pin "58") (pinfunction "PB6_58") (pintype "passive"))
      (node (ref "J108") (pin "1") (pinfunction "1_1") (pintype "passive"))
      (node (ref "R119") (pin "1") (pinfunction "1_1") (pintype "passive"))
    )
    (net (code "30") (name "/I2C1_SDA") (class "Default")
      (node (ref "IC101") (pin "59") (pinfunction "PB7_59") (pintype "passive"))
      (node (ref "J108") (pin "2") (pinfunction "2_2") (pintype "passive"))
      (node (ref "R118") (pin "1") (pinfunction "1_1") (pintype "passive"))
    )
    (net (code "31") (name "/I_OUT") (class "Default")
      (node (ref "IC101") (pin "17") (pinfunction "PA3_17") (pintype "passive"))
    )
    (net (code "32") (name "/L1") (class "Default")
      (node (ref "IC101") (pin "23") (pinfunction "PA7_23") (pintype "passive"))
    )
    (net (code "33") (name "/L2") (class "Default")
      (node (ref "IC101") (pin "35") (pinfunction "PB14_35") (pintype "passive"))
    )
    (net (code "34") (name "/LED1") (class "Default")
      (node (ref "IC101") (pin "2") (pinfunction "PC13_2") (pintype "passive"))
      (node (ref "LED101") (pin "2") (pinfunction "A_2") (pintype "passive"))
    )
    (net (code "35") (name "/LED2") (class "Default")
      (node (ref "IC101") (pin "3") (pinfunction "PC14_3") (pintype "passive"))
      (node (ref "LED103") (pin "2") (pinfunction "A_2") (pintype "passive"))
    )
    (net (code "36") (name "/LED3") (class "Default")
      (node (ref "IC101") (pin "4") (pinfunction "PC15_4") (pintype "passive"))
      (node (ref "LED104") (pin "2") (pinfunction "A_2") (pintype "passive"))
    )
    (net (code "37") (name "/PH0") (class "Default")
      (node (ref "C139") (pin "2") (pinfunction "2_2") (pintype "passive"))
      (node (ref "IC101") (pin "5") (pinfunction "PH0_5") (pintype "passive"))
      (node (ref "Y100") (pin "1") (pinfunction "HOT_1_1") (pintype "passive"))
    )
    (net (code "38") (name "/PH1") (class "Default")
      (node (ref "C140") (pin "2") (pinfunction "2_2") (pintype "passive"))
      (node (ref "IC101") (pin "6") (pinfunction "PH1_6") (pintype "passive"))
      (node (ref "Y100") (pin "3") (pinfunction "HOT_2_3") (pintype "passive"))
    )
    (net (code "39") (name "/PSU_RS_RX") (class "Default")
      (node (ref "IC100") (pin "13") (pinfunction "RIN1_13") (pintype "input"))
      (node (ref "J107") (pin "3") (pinfunction "3_3") (pintype "passive"))
    )
    (net (code "40") (name "/PSU_RS_TX") (class "Default")
      (node (ref "IC100") (pin "14") (pinfunction "DOUT1_14") (pintype "output"))
      (node (ref "J107") (pin "2") (pinfunction "2_2") (pintype "passive"))
    )
    (net (code "41") (name "/SPI1_MISO") (class "Default")
      (node (ref "IC101") (pin "56") (pinfunction "PB4_56") (pintype "passive"))
      (node (ref "J108") (pin "4") (pinfunction "4_4") (pintype "passive"))
    )
    (net (code "42") (name "/SPI1_MOSI") (class "Default")
      (node (ref "IC101") (pin "57") (pinfunction "PB5_57") (pintype "passive"))
      (node (ref "J108") (pin "5") (pinfunction "5_5") (pintype "passive"))
    )
    (net (code "43") (name "/SPI1_SCK") (class "Default")
      (node (ref "IC101") (pin "55") (pinfunction "PB3_55") (pintype "passive"))
      (node (ref "J108") (pin "3") (pinfunction "3_3") (pintype "passive"))
    )
    (net (code "44") (name "/SPI_SS1") (class "Default")
      (node (ref "IC101") (pin "54") (pinfunction "PD2_54") (pintype "passive"))
      (node (ref "J108") (pin "6") (pinfunction "6_6") (pintype "passive"))
    )
    (net (code "45") (name "/SPI_SS2") (class "Default")
      (node (ref "IC101") (pin "53") (pinfunction "PC12_53") (pintype "passive"))
      (node (ref "J108") (pin "7") (pinfunction "7_7") (pintype "passive"))
    )
    (net (code "46") (name "/SPI_SS3") (class "Default")
      (node (ref "IC101") (pin "52") (pinfunction "PC11_52") (pintype "passive"))
      (node (ref "J108") (pin "8") (pinfunction "8_8") (pintype "passive"))
    )
    (net (code "47") (name "/SYS_JTCK_SWCLK") (class "Default")
      (node (ref "IC101") (pin "49") (pinfunction "PA14_49") (pintype "passive"))
      (node (ref "R104") (pin "1") (pinfunction "1_1") (pintype "passive"))
    )
    (net (code "48") (name "/SYS_JTMS_SWDIO") (class "Default")
      (node (ref "IC101") (pin "46") (pinfunction "PA13_46") (pintype "passive"))
      (node (ref "R105") (pin "1") (pinfunction "1_1") (pintype "passive"))
    )
    (net (code "49") (name "/TIM1_CH1") (class "Default")
      (node (ref "IC101") (pin "41") (pinfunction "PA8_41") (pintype "passive"))
      (node (ref "J105") (pin "1") (pinfunction "1_1") (pintype "passive"))
    )
    (net (code "50") (name "/TIM5_CH1") (class "Default")
      (node (ref "IC101") (pin "14") (pinfunction "PA0_WKUP_14") (pintype "passive"))
      (node (ref "J105") (pin "2") (pinfunction "2_2") (pintype "passive"))
    )
    (net (code "51") (name "/TIM5_CH2") (class "Default")
      (node (ref "IC101") (pin "15") (pinfunction "PA1_15") (pintype "passive"))
      (node (ref "J105") (pin "3") (pinfunction "3_3") (pintype "passive"))
    )
    (net (code "52") (name "/TIM5_CH3") (class "Default")
      (node (ref "IC101") (pin "16") (pinfunction "PA2_16") (pintype "passive"))
      (node (ref "J105") (pin "4") (pinfunction "4_4") (pintype "passive"))
    )
    (net (code "53") (name "/USART1_RX") (class "Default")
      (node (ref "IC100") (pin "12") (pinfunction "ROUT1_12") (pintype "output"))
      (node (ref "IC101") (pin "43") (pinfunction "PA10_43") (pintype "passive"))
      (node (ref "R120") (pin "2") (pinfunction "2_2") (pintype "passive"))
    )
    (net (code "54") (name "/USART1_TX") (class "Default")
      (node (ref "IC100") (pin "11") (pinfunction "DIN1_11") (pintype "input"))
      (node (ref "IC101") (pin "42") (pinfunction "PA9_42") (pintype "passive"))
      (node (ref "R116") (pin "2") (pinfunction "2_2") (pintype "passive"))
    )
    (net (code "55") (name "/USB_OTG_FS_DM") (class "Default")
      (node (ref "IC101") (pin "44") (pinfunction "PA11_44") (pintype "passive"))
      (node (ref "R126") (pin "2") (pinfunction "2_2") (pintype "passive"))
    )
    (net (code "56") (name "/USB_OTG_FS_DP") (class "Default")
      (node (ref "IC101") (pin "45") (pinfunction "PA12_45") (pintype "passive"))
      (node (ref "R128") (pin "2") (pinfunction "2_2") (pintype "passive"))
    )
    (net (code "57") (name "/nRST") (class "Default")
      (node (ref "C122") (pin "2") (pinfunction "2_2") (pintype "passive"))
      (node (ref "IC101") (pin "7") (pinfunction "NRST_7") (pintype "passive"))
      (node (ref "J106") (pin "15") (pinfunction "15_15") (pintype "passive"))
      (node (ref "R127") (pin "1") (pinfunction "1_1") (pintype "passive"))
      (node (ref "S100") (pin "3") (pinfunction "COM_1_3") (pintype "passive"))
      (node (ref "S100") (pin "4") (pinfunction "COM_2_4") (pintype "passive"))
    )
    (net (code "58") (name "5V") (class "Default")
      (node (ref "C129") (pin "1") (pinfunction "+_1") (pintype "passive"))
      (node (ref "C132") (pin "1") (pinfunction "1_1") (pintype "passive"))
      (node (ref "C133") (pin "2") (pinfunction "2_2") (pintype "passive"))
      (node (ref "C138") (pin "2") (pinfunction "2_2") (pintype "passive"))
      (node (ref "IC103") (pin "1") (pinfunction "IN_1") (pintype "passive"))
      (node (ref "IC103") (pin "3") (pinfunction "EN_3") (pintype "passive"))
      (node (ref "IC104") (pin "3") (pinfunction "OUTPUT_3") (pintype "passive"))
      (node (ref "IC105") (pin "3") (pinfunction "VIN_3") (pintype "passive"))
      (node (ref "J104") (pin "3") (pinfunction "3_3") (pintype "passive"))
      (node (ref "J106") (pin "16") (pinfunction "16_16") (pintype "passive"))
      (node (ref "J108") (pin "9") (pinfunction "9_9") (pintype "passive"))
    )
    (net (code "59") (name "8V") (class "Default")
      (node (ref "C136") (pin "2") (pinfunction "2_2") (pintype "passive"))
      (node (ref "IC106") (pin "2") (pinfunction "VOUT_2") (pintype "passive"))
      (node (ref "LED107") (pin "2") (pinfunction "A_2") (pintype "passive"))
      (node (ref "R129") (pin "2") (pinfunction "2_2") (pintype "passive"))
    )
    (net (code "60") (name "12V") (class "Default")
      (node (ref "C135") (pin "2") (pinfunction "2_2") (pintype "passive"))
      (node (ref "IC104") (pin "1") (pinfunction "INPUT_1") (pintype "passive"))
      (node (ref "IC106") (pin "3") (pinfunction "VIN_3") (pintype "passive"))
    )
    (net (code "61") (name "AVCC") (class "Default")
      (node (ref "C130") (pin "2") (pinfunction "2_2") (pintype "passive"))
      (node (ref "C131") (pin "2") (pinfunction "2_2") (pintype "passive"))
      (node (ref "C134") (pin "2") (pinfunction "2_2") (pintype "passive"))
      (node (ref "IC101") (pin "13") (pinfunction "VDDA_13") (pintype "passive"))
      (node (ref "IC103") (pin "5") (pinfunction "OUT_5") (pintype "passive"))
    )
    (net (code "62") (name "GND") (class "Default")
      (node (ref "C100") (pin "1") (pinfunction "1_1") (pintype "passive"))
      (node (ref "C101") (pin "1") (pinfunction "1_1") (pintype "passive"))
      (node (ref "C103") (pin "1") (pinfunction "1_1") (pintype "passive"))
      (node (ref "C104") (pin "1") (pinfunction "1_1") (pintype "passive"))
      (node (ref "C107") (pin "1") (pinfunction "1_1") (pintype "passive"))
      (node (ref "C108") (pin "1") (pinfunction "1_1") (pintype "passive"))
      (node (ref "C109") (pin "1") (pinfunction "1_1") (pintype "passive"))
      (node (ref "C110") (pin "2") (pinfunction "2_2") (pintype "passive"))
      (node (ref "C111") (pin "2") (pinfunction "2_2") (pintype "passive"))
      (node (ref "C112") (pin "1") (pinfunction "1_1") (pintype "passive"))
      (node (ref "C113") (pin "1") (pinfunction "1_1") (pintype "passive"))
      (node (ref "C114") (pin "1") (pinfunction "1_1") (pintype "passive"))
      (node (ref "C115") (pin "1") (pinfunction "1_1") (pintype "passive"))
      (node (ref "C116") (pin "1") (pinfunction "1_1") (pintype "passive"))
      (node (ref "C117") (pin "1") (pinfunction "1_1") (pintype "passive"))
      (node (ref "C118") (pin "1") (pinfunction "1_1") (pintype "passive"))
      (node (ref "C119") (pin "1") (pinfunction "1_1") (pintype "passive"))
      (node (ref "C120") (pin "1") (pinfunction "1_1") (pintype "passive"))
      (node (ref "C121") (pin "1") (pinfunction "1_1") (pintype "passive"))
      (node (ref "C122") (pin "1") (pinfunction "1_1") (pintype "passive"))
      (node (ref "C123") (pin "1") (pinfunction "1_1") (pintype "passive"))
      (node (ref "C124") (pin "1") (pinfunction "1_1") (pintype "passive"))
      (node (ref "C125") (pin "1") (pinfunction "1_1") (pintype "passive"))
      (node (ref "C126") (pin "1") (pinfunction "1_1") (pintype "passive"))
      (node (ref "C127") (pin "1") (pinfunction "1_1") (pintype "passive"))
      (node (ref "C128") (pin "1") (pinfunction "1_1") (pintype "passive"))
      (node (ref "C129") (pin "2") (pinfunction "-_2") (pintype "passive"))
      (node (ref "C130") (pin "1") (pinfunction "1_1") (pintype "passive"))
      (node (ref "C131") (pin "1") (pinfunction "1_1") (pintype "passive"))
      (node (ref "C132") (pin "2") (pinfunction "2_2") (pintype "passive"))
      (node (ref "C133") (pin "1") (pinfunction "1_1") (pintype "passive"))
      (node (ref "C134") (pin "1") (pinfunction "1_1") (pintype "passive"))
      (node (ref "C135") (pin "1") (pinfunction "1_1") (pintype "passive"))
      (node (ref "C136") (pin "1") (pinfunction "1_1") (pintype "passive"))
      (node (ref "C137") (pin "1") (pinfunction "1_1") (pintype "passive"))
      (node (ref "C138") (pin "1") (pinfunction "1_1") (pintype "passive"))
      (node (ref "C139") (pin "1") (pinfunction "1_1") (pintype "passive"))
      (node (ref "C140") (pin "1") (pinfunction "1_1") (pintype "passive"))
      (node (ref "D100") (pin "1") (pinfunction "COMMON_A_1") (pintype "passive"))
      (node (ref "IC100") (pin "10") (pinfunction "DIN2_10") (pintype "input"))
      (node (ref "IC100") (pin "15") (pinfunction "GND_15") (pintype "passive"))
      (node (ref "IC100") (pin "8") (pinfunction "RIN2_8") (pintype "input"))
      (node (ref "IC101") (pin "12") (pinfunction "VSSA_12") (pintype "passive"))
      (node (ref "IC101") (pin "18") (pinfunction "VSS_1_18") (pintype "passive"))
      (node (ref "IC101") (pin "63") (pinfunction "VSS_2_63") (pintype "passive"))
      (node (ref "IC102") (pin "2") (pinfunction "GND_2") (pintype "passive"))
      (node (ref "IC103") (pin "2") (pinfunction "GND_2") (pintype "passive"))
      (node (ref "IC104") (pin "4") (pinfunction "GND_4") (pintype "passive"))
      (node (ref "IC105") (pin "1") (pinfunction "GND/ADJ_1") (pintype "passive"))
      (node (ref "J104") (pin "4") (pinfunction "4_4") (pintype "passive"))
      (node (ref "J105") (pin "6") (pinfunction "6_6") (pintype "passive"))
      (node (ref "J106") (pin "19") (pinfunction "19_19") (pintype "passive"))
      (node (ref "J106") (pin "20") (pinfunction "20_20") (pintype "passive"))
      (node (ref "J107") (pin "5") (pinfunction "5_5") (pintype "passive"))
      (node (ref "J108") (pin "10") (pinfunction "10_10") (pintype "passive"))
      (node (ref "J109") (pin "3") (pinfunction "3_3") (pintype "passive"))
      (node (ref "J110") (pin "5") (pinfunction "5_5") (pintype "passive"))
      (node (ref "J110") (pin "MH1") (pinfunction "MH1_MH1") (pintype "passive"))
      (node (ref "J110") (pin "MH2") (pinfunction "MH2_MH2") (pintype "passive"))
      (node (ref "R117") (pin "2") (pinfunction "2_2") (pintype "passive"))
      (node (ref "R121") (pin "2") (pinfunction "2_2") (pintype "passive"))
      (node (ref "R122") (pin "2") (pinfunction "2_2") (pintype "passive"))
      (node (ref "R130") (pin "1") (pinfunction "1_1") (pintype "passive"))
      (node (ref "R131") (pin "1") (pinfunction "1_1") (pintype "passive"))
      (node (ref "R132") (pin "1") (pinfunction "1_1") (pintype "passive"))
      (node (ref "R133") (pin "1") (pinfunction "1_1") (pintype "passive"))
      (node (ref "S100") (pin "1") (pinfunction "NO_1_1") (pintype "passive"))
      (node (ref "S100") (pin "2") (pinfunction "NO_2_2") (pintype "passive"))
      (node (ref "Y100") (pin "2") (pinfunction "NC_1_2") (pintype "passive"))
      (node (ref "Y100") (pin "4") (pinfunction "NC_2_4") (pintype "passive"))
    )
    (net (code "63") (name "Net-(D100-K_1)") (class "Default")
      (node (ref "D100") (pin "2") (pinfunction "K_1_2") (pintype "passive"))
      (node (ref "J110") (pin "2") (pinfunction "2_2") (pintype "passive"))
      (node (ref "R126") (pin "1") (pinfunction "1_1") (pintype "passive"))
    )
    (net (code "64") (name "Net-(D100-K_2)") (class "Default")
      (node (ref "D100") (pin "3") (pinfunction "K_2_3") (pintype "passive"))
      (node (ref "J110") (pin "3") (pinfunction "3_3") (pintype "passive"))
      (node (ref "R128") (pin "1") (pinfunction "1_1") (pintype "passive"))
    )
    (net (code "65") (name "Net-(D100-K_3)") (class "Default")
      (node (ref "D100") (pin "4") (pinfunction "K_3_4") (pintype "passive"))
      (node (ref "J110") (pin "1") (pinfunction "1_1") (pintype "passive"))
    )
    (net (code "66") (name "Net-(IC100-C1+)") (class "Default")
      (node (ref "C102") (pin "1") (pinfunction "1_1") (pintype "passive"))
      (node (ref "IC100") (pin "1") (pinfunction "C1+_1") (pintype "passive"))
    )
    (net (code "67") (name "Net-(IC100-C1-)") (class "Default")
      (node (ref "C102") (pin "2") (pinfunction "2_2") (pintype "passive"))
      (node (ref "IC100") (pin "3") (pinfunction "C1-_3") (pintype "passive"))
    )
    (net (code "68") (name "Net-(IC100-C2+)") (class "Default")
      (node (ref "C106") (pin "1") (pinfunction "1_1") (pintype "passive"))
      (node (ref "IC100") (pin "4") (pinfunction "C2+_4") (pintype "passive"))
    )
    (net (code "69") (name "Net-(IC100-C2-)") (class "Default")
      (node (ref "C106") (pin "2") (pinfunction "2_2") (pintype "passive"))
      (node (ref "IC100") (pin "5") (pinfunction "C2-_5") (pintype "passive"))
    )
    (net (code "70") (name "Net-(IC100-V+)") (class "Default")
      (node (ref "C105") (pin "2") (pinfunction "2_2") (pintype "passive"))
      (node (ref "IC100") (pin "2") (pinfunction "V+_2") (pintype "passive"))
    )
    (net (code "71") (name "Net-(IC100-V-)") (class "Default")
      (node (ref "C107") (pin "2") (pinfunction "2_2") (pintype "passive"))
      (node (ref "IC100") (pin "6") (pinfunction "V-_6") (pintype "passive"))
    )
    (net (code "72") (name "Net-(IC101A-VCAP_1)") (class "Default")
      (node (ref "C121") (pin "2") (pinfunction "2_2") (pintype "passive"))
      (node (ref "IC101") (pin "31") (pinfunction "VCAP_1_31") (pintype "passive"))
    )
    (net (code "73") (name "Net-(IC101A-VCAP_2)") (class "Default")
      (node (ref "C120") (pin "2") (pinfunction "2_2") (pintype "passive"))
      (node (ref "IC101") (pin "47") (pinfunction "VCAP_2_47") (pintype "passive"))
    )
    (net (code "74") (name "Net-(IC106-ADJUST)") (class "Default")
      (node (ref "IC106") (pin "1") (pinfunction "ADJUST_1") (pintype "passive"))
      (node (ref "R129") (pin "1") (pinfunction "1_1") (pintype "passive"))
      (node (ref "R131") (pin "2") (pinfunction "2_2") (pintype "passive"))
    )
    (net (code "75") (name "Net-(J104-Pad1)") (class "Default")
      (node (ref "J104") (pin "1") (pinfunction "1_1") (pintype "passive"))
      (node (ref "R104") (pin "2") (pinfunction "2_2") (pintype "passive"))
    )
    (net (code "76") (name "Net-(J104-Pad2)") (class "Default")
      (node (ref "J104") (pin "2") (pinfunction "2_2") (pintype "passive"))
      (node (ref "R105") (pin "2") (pinfunction "2_2") (pintype "passive"))
    )
    (net (code "77") (name "Net-(J106-Pad1)") (class "Default")
      (node (ref "J106") (pin "1") (pinfunction "1_1") (pintype "passive"))
      (node (ref "R100") (pin "2") (pinfunction "2_2") (pintype "passive"))
    )
    (net (code "78") (name "Net-(J106-Pad2)") (class "Default")
      (node (ref "J106") (pin "2") (pinfunction "2_2") (pintype "passive"))
      (node (ref "R101") (pin "2") (pinfunction "2_2") (pintype "passive"))
    )
    (net (code "79") (name "Net-(J106-Pad3)") (class "Default")
      (node (ref "J106") (pin "3") (pinfunction "3_3") (pintype "passive"))
      (node (ref "R102") (pin "2") (pinfunction "2_2") (pintype "passive"))
    )
    (net (code "80") (name "Net-(J106-Pad4)") (class "Default")
      (node (ref "J106") (pin "4") (pinfunction "4_4") (pintype "passive"))
      (node (ref "R103") (pin "2") (pinfunction "2_2") (pintype "passive"))
    )
    (net (code "81") (name "Net-(J106-Pad5)") (class "Default")
      (node (ref "J106") (pin "5") (pinfunction "5_5") (pintype "passive"))
      (node (ref "R106") (pin "2") (pinfunction "2_2") (pintype "passive"))
    )
    (net (code "82") (name "Net-(J106-Pad6)") (class "Default")
      (node (ref "J106") (pin "6") (pinfunction "6_6") (pintype "passive"))
      (node (ref "R107") (pin "2") (pinfunction "2_2") (pintype "passive"))
    )
    (net (code "83") (name "Net-(J106-Pad7)") (class "Default")
      (node (ref "J106") (pin "7") (pinfunction "7_7") (pintype "passive"))
      (node (ref "R108") (pin "2") (pinfunction "2_2") (pintype "passive"))
    )
    (net (code "84") (name "Net-(J106-Pad8)") (class "Default")
      (node (ref "J106") (pin "8") (pinfunction "8_8") (pintype "passive"))
      (node (ref "R109") (pin "2") (pinfunction "2_2") (pintype "passive"))
    )
    (net (code "85") (name "Net-(J106-Pad9)") (class "Default")
      (node (ref "J106") (pin "9") (pinfunction "9_9") (pintype "passive"))
      (node (ref "R110") (pin "2") (pinfunction "2_2") (pintype "passive"))
    )
    (net (code "86") (name "Net-(J106-Pad10)") (class "Default")
      (node (ref "J106") (pin "10") (pinfunction "10_10") (pintype "passive"))
      (node (ref "R111") (pin "2") (pinfunction "2_2") (pintype "passive"))
    )
    (net (code "87") (name "Net-(J106-Pad11)") (class "Default")
      (node (ref "J106") (pin "11") (pinfunction "11_11") (pintype "passive"))
      (node (ref "R112") (pin "2") (pinfunction "2_2") (pintype "passive"))
    )
    (net (code "88") (name "Net-(J106-Pad12)") (class "Default")
      (node (ref "J106") (pin "12") (pinfunction "12_12") (pintype "passive"))
      (node (ref "R113") (pin "2") (pinfunction "2_2") (pintype "passive"))
    )
    (net (code "89") (name "Net-(J106-Pad13)") (class "Default")
      (node (ref "J106") (pin "13") (pinfunction "13_13") (pintype "passive"))
      (node (ref "R114") (pin "2") (pinfunction "2_2") (pintype "passive"))
    )
    (net (code "90") (name "Net-(J106-Pad14)") (class "Default")
      (node (ref "J106") (pin "14") (pinfunction "14_14") (pintype "passive"))
      (node (ref "R115") (pin "2") (pinfunction "2_2") (pintype "passive"))
    )
    (net (code "91") (name "Net-(LED100-K)") (class "Default")
      (node (ref "LED100") (pin "1") (pinfunction "K_1") (pintype "passive"))
      (node (ref "R116") (pin "1") (pinfunction "1_1") (pintype "passive"))
    )
    (net (code "92") (name "Net-(LED101-K)") (class "Default")
      (node (ref "LED101") (pin "1") (pinfunction "K_1") (pintype "passive"))
      (node (ref "R117") (pin "1") (pinfunction "1_1") (pintype "passive"))
    )
    (net (code "93") (name "Net-(LED102-K)") (class "Default")
      (node (ref "LED102") (pin "1") (pinfunction "K_1") (pintype "passive"))
      (node (ref "R120") (pin "1") (pinfunction "1_1") (pintype "passive"))
    )
    (net (code "94") (name "Net-(LED103-K)") (class "Default")
      (node (ref "LED103") (pin "1") (pinfunction "K_1") (pintype "passive"))
      (node (ref "R121") (pin "1") (pinfunction "1_1") (pintype "passive"))
    )
    (net (code "95") (name "Net-(LED104-K)") (class "Default")
      (node (ref "LED104") (pin "1") (pinfunction "K_1") (pintype "passive"))
      (node (ref "R122") (pin "1") (pinfunction "1_1") (pintype "passive"))
    )
    (net (code "96") (name "Net-(LED105-A)") (class "Default")
      (node (ref "LED105") (pin "2") (pinfunction "A_2") (pintype "passive"))
      (node (ref "R124") (pin "2") (pinfunction "2_2") (pintype "passive"))
    )
    (net (code "97") (name "Net-(LED106-A)") (class "Default")
      (node (ref "LED106") (pin "2") (pinfunction "A_2") (pintype "passive"))
      (node (ref "R125") (pin "2") (pinfunction "2_2") (pintype "passive"))
    )
    (net (code "98") (name "Net-(LED107-K)") (class "Default")
      (node (ref "LED107") (pin "1") (pinfunction "K_1") (pintype "passive"))
      (node (ref "R130") (pin "2") (pinfunction "2_2") (pintype "passive"))
    )
    (net (code "99") (name "Net-(LED108-K)") (class "Default")
      (node (ref "LED108") (pin "1") (pinfunction "K_1") (pintype "passive"))
      (node (ref "R132") (pin "2") (pinfunction "2_2") (pintype "passive"))
    )
    (net (code "100") (name "VCC") (class "Default")
      (node (ref "C105") (pin "1") (pinfunction "1_1") (pintype "passive"))
      (node (ref "C110") (pin "1") (pinfunction "1_1") (pintype "passive"))
      (node (ref "C111") (pin "1") (pinfunction "1_1") (pintype "passive"))
      (node (ref "C123") (pin "2") (pinfunction "2_2") (pintype "passive"))
      (node (ref "C124") (pin "2") (pinfunction "2_2") (pintype "passive"))
      (node (ref "C125") (pin "2") (pinfunction "2_2") (pintype "passive"))
      (node (ref "C126") (pin "2") (pinfunction "2_2") (pintype "passive"))
      (node (ref "C127") (pin "2") (pinfunction "2_2") (pintype "passive"))
      (node (ref "C128") (pin "2") (pinfunction "2_2") (pintype "passive"))
      (node (ref "C137") (pin "2") (pinfunction "2_2") (pintype "passive"))
      (node (ref "IC100") (pin "16") (pinfunction "VCC_16") (pintype "passive"))
      (node (ref "IC101") (pin "1") (pinfunction "VBAT_1") (pintype "passive"))
      (node (ref "IC101") (pin "19") (pinfunction "VDD_1_19") (pintype "passive"))
      (node (ref "IC101") (pin "32") (pinfunction "VDD_2_32") (pintype "passive"))
      (node (ref "IC101") (pin "48") (pinfunction "VDD_3_48") (pintype "passive"))
      (node (ref "IC101") (pin "64") (pinfunction "VDD_4_64") (pintype "passive"))
      (node (ref "IC102") (pin "3") (pinfunction "VCC_3") (pintype "passive"))
      (node (ref "IC105") (pin "2") (pinfunction "VOUT_2") (pintype "passive"))
      (node (ref "IC105") (pin "4") (pinfunction "NC_4") (pintype "passive"))
      (node (ref "J105") (pin "5") (pinfunction "5_5") (pintype "passive"))
      (node (ref "J106") (pin "18") (pinfunction "18_18") (pintype "passive"))
      (node (ref "LED100") (pin "2") (pinfunction "A_2") (pintype "passive"))
      (node (ref "LED102") (pin "2") (pinfunction "A_2") (pintype "passive"))
      (node (ref "LED108") (pin "2") (pinfunction "A_2") (pintype "passive"))
      (node (ref "R118") (pin "2") (pinfunction "2_2") (pintype "passive"))
      (node (ref "R119") (pin "2") (pinfunction "2_2") (pintype "passive"))
      (node (ref "R124") (pin "1") (pinfunction "1_1") (pintype "passive"))
      (node (ref "R125") (pin "1") (pinfunction "1_1") (pintype "passive"))
      (node (ref "R127") (pin "2") (pinfunction "2_2") (pintype "passive"))
      (node (ref "S101") (pin "3") (pinfunction "COM_1_3") (pintype "passive"))
      (node (ref "S101") (pin "4") (pinfunction "COM_2_4") (pintype "passive"))
    )
    (net (code "101") (name "unconnected-(IC100-DOUT2-Pad7)") (class "Default")
      (node (ref "IC100") (pin "7") (pinfunction "DOUT2_7") (pintype "output"))
    )
    (net (code "102") (name "unconnected-(IC100-ROUT2-Pad9)") (class "Default")
      (node (ref "IC100") (pin "9") (pinfunction "ROUT2_9") (pintype "output"))
    )
    (net (code "103") (name "unconnected-(IC102-S-Pad8)") (class "Default")
      (node (ref "IC102") (pin "8") (pinfunction "S_8") (pintype "passive"))
    )
    (net (code "104") (name "unconnected-(IC102-VREF-Pad5)") (class "Default")
      (node (ref "IC102") (pin "5") (pinfunction "VREF_5") (pintype "passive"))
    )
    (net (code "105") (name "unconnected-(IC103-N{slash}C-Pad4)") (class "Default")
      (node (ref "IC103") (pin "4") (pinfunction "N/C_4") (pintype "passive"))
    )
    (net (code "106") (name "unconnected-(J100-0-PadJ?)") (class "Default")
      (node (ref "J100") (pin "J?") (pinfunction "0_J?") (pintype "passive"))
    )
    (net (code "107") (name "unconnected-(J101-0-PadJ?)") (class "Default")
      (node (ref "J101") (pin "J?") (pinfunction "0_J?") (pintype "passive"))
    )
    (net (code "108") (name "unconnected-(J102-0-PadJ?)") (class "Default")
      (node (ref "J102") (pin "J?") (pinfunction "0_J?") (pintype "passive"))
    )
    (net (code "109") (name "unconnected-(J103-0-PadJ?)") (class "Default")
      (node (ref "J103") (pin "J?") (pinfunction "0_J?") (pintype "passive"))
    )
    (net (code "110") (name "unconnected-(J107-Pad1)") (class "Default")
      (node (ref "J107") (pin "1") (pinfunction "1_1") (pintype "passive"))
    )
    (net (code "111") (name "unconnected-(J107-Pad4)") (class "Default")
      (node (ref "J107") (pin "4") (pinfunction "4_4") (pintype "passive"))
    )
    (net (code "112") (name "unconnected-(J107-Pad6)") (class "Default")
      (node (ref "J107") (pin "6") (pinfunction "6_6") (pintype "passive"))
    )
    (net (code "113") (name "unconnected-(J107-Pad7)") (class "Default")
      (node (ref "J107") (pin "7") (pinfunction "7_7") (pintype "passive"))
    )
    (net (code "114") (name "unconnected-(J107-Pad8)") (class "Default")
      (node (ref "J107") (pin "8") (pinfunction "8_8") (pintype "passive"))
    )
    (net (code "115") (name "unconnected-(J107-Pad9)") (class "Default")
      (node (ref "J107") (pin "9") (pinfunction "9_9") (pintype "passive"))
    )
    (net (code "116") (name "unconnected-(J107-PadMH1)") (class "Default")
      (node (ref "J107") (pin "MH1") (pinfunction "MH1_MH1") (pintype "passive"))
    )
    (net (code "117") (name "unconnected-(J107-PadMH2)") (class "Default")
      (node (ref "J107") (pin "MH2") (pinfunction "MH2_MH2") (pintype "passive"))
    )
    (net (code "118") (name "unconnected-(J110-Pad4)") (class "Default")
      (node (ref "J110") (pin "4") (pinfunction "4_4") (pintype "passive"))
    )
  )
)
